# QCopterRC_KEY_Sch.net
KiCad netlist of a schematic drawn in Altium Designer
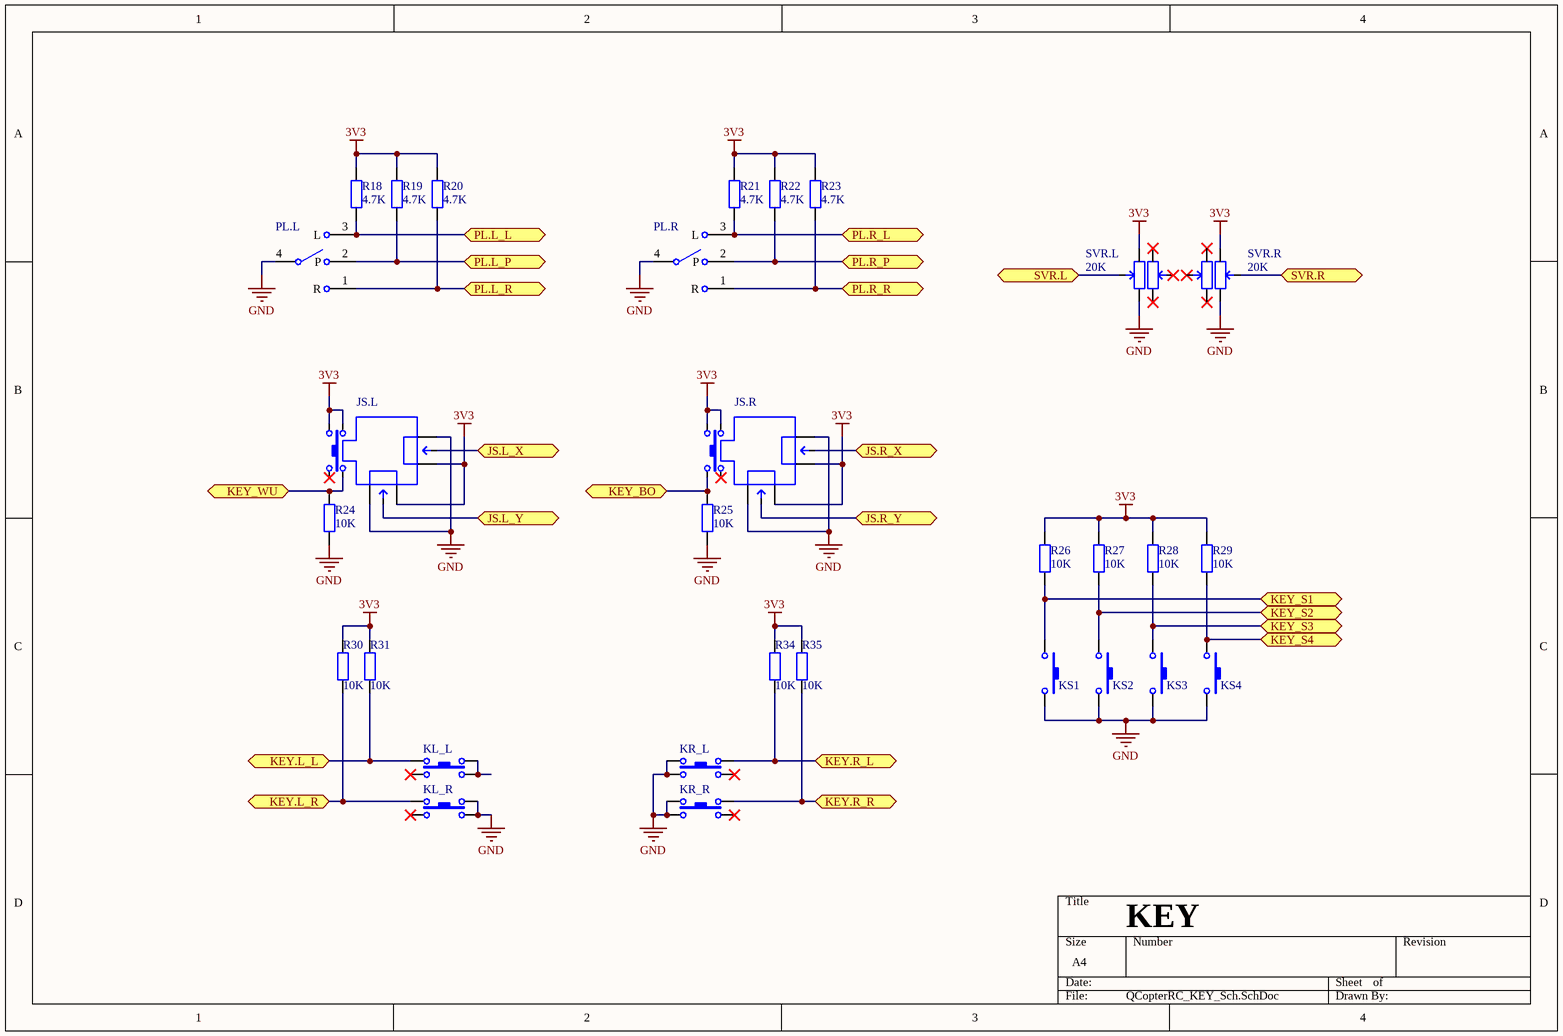
[diagram p0: QCopterRC_KEY_Sch.SchDoc]

(export (version "E")
  (design (tool "Eeschema 10.0.6"))
  (components
    (comp (ref "JS.L")
      (value "JoyStick")
      (footprint "PCB_Switch:JoyStick")
      (libsource (lib "SCH_Switch") (part "JoyStick"))
    )
    (comp (ref "JS.R")
      (value "JoyStick")
      (footprint "PCB_Switch:JoyStick")
      (libsource (lib "SCH_Switch") (part "JoyStick"))
    )
    (comp (ref "KL_L")
      (value "BT_TACT_12X12_D180")
      (footprint "PCB_Switch:BT_TACT_12X12_D180")
      (description "Switch")
      (libsource (lib "SCH_Switch") (part "BT_TACT_12X12_D180"))
    )
    (comp (ref "KL_R")
      (value "BT_TACT_12X12_D180")
      (footprint "PCB_Switch:BT_TACT_12X12_D180")
      (description "Switch")
      (libsource (lib "SCH_Switch") (part "BT_TACT_12X12_D180"))
    )
    (comp (ref "KR_L")
      (value "BT_TACT_12X12_D180")
      (footprint "PCB_Switch:BT_TACT_12X12_D180")
      (description "Switch")
      (libsource (lib "SCH_Switch") (part "BT_TACT_12X12_D180"))
    )
    (comp (ref "KR_R")
      (value "BT_TACT_12X12_D180")
      (footprint "PCB_Switch:BT_TACT_12X12_D180")
      (description "Switch")
      (libsource (lib "SCH_Switch") (part "BT_TACT_12X12_D180"))
    )
    (comp (ref "KS1")
      (value "BT_TACT_3x6_180")
      (footprint "PCB_Switch:BT_TACT_3x6_180")
      (description "Switch")
      (libsource (lib "SCH_Switch") (part "BT_TACT_3x6_180"))
    )
    (comp (ref "KS2")
      (value "BT_TACT_3x6_180")
      (footprint "PCB_Switch:BT_TACT_3x6_180")
      (description "Switch")
      (libsource (lib "SCH_Switch") (part "BT_TACT_3x6_180"))
    )
    (comp (ref "KS3")
      (value "BT_TACT_3x6_180")
      (footprint "PCB_Switch:BT_TACT_3x6_180")
      (description "Switch")
      (libsource (lib "SCH_Switch") (part "BT_TACT_3x6_180"))
    )
    (comp (ref "KS4")
      (value "BT_TACT_3x6_180")
      (footprint "PCB_Switch:BT_TACT_3x6_180")
      (description "Switch")
      (libsource (lib "SCH_Switch") (part "BT_TACT_3x6_180"))
    )
    (comp (ref "PL.L")
      (value "BT_PushLever_11*12_90")
      (footprint "PCB_Switch:BT_PushLever_11*12_90")
      (description "Switch")
      (libsource (lib "SCH_Switch") (part "BT_PushLever_11*12_90"))
    )
    (comp (ref "PL.R")
      (value "BT_PushLever_11*12_90")
      (footprint "PCB_Switch:BT_PushLever_11*12_90")
      (description "Switch")
      (libsource (lib "SCH_Switch") (part "BT_PushLever_11*12_90"))
    )
    (comp (ref "R18")
      (value "4.7K")
      (footprint "PCB_Passive:RES_0603")
      (description "Resistor")
      (fields (field (name "Comment") "Res_0603"))
      (libsource (lib "SCH_Passive") (part "Res_0603"))
    )
    (comp (ref "R19")
      (value "4.7K")
      (footprint "PCB_Passive:RES_0603")
      (description "Resistor")
      (fields (field (name "Comment") "Res_0603"))
      (libsource (lib "SCH_Passive") (part "Res_0603"))
    )
    (comp (ref "R20")
      (value "4.7K")
      (footprint "PCB_Passive:RES_0603")
      (description "Resistor")
      (fields (field (name "Comment") "Res_0603"))
      (libsource (lib "SCH_Passive") (part "Res_0603"))
    )
    (comp (ref "R21")
      (value "4.7K")
      (footprint "PCB_Passive:RES_0603")
      (description "Resistor")
      (fields (field (name "Comment") "Res_0603"))
      (libsource (lib "SCH_Passive") (part "Res_0603"))
    )
    (comp (ref "R22")
      (value "4.7K")
      (footprint "PCB_Passive:RES_0603")
      (description "Resistor")
      (fields (field (name "Comment") "Res_0603"))
      (libsource (lib "SCH_Passive") (part "Res_0603"))
    )
    (comp (ref "R23")
      (value "4.7K")
      (footprint "PCB_Passive:RES_0603")
      (description "Resistor")
      (fields (field (name "Comment") "Res_0603"))
      (libsource (lib "SCH_Passive") (part "Res_0603"))
    )
    (comp (ref "R24")
      (value "10K")
      (footprint "PCB_Passive:RES_0603")
      (description "Resistor")
      (fields (field (name "Comment") "Res_0603"))
      (libsource (lib "SCH_Passive") (part "Res_0603"))
    )
    (comp (ref "R25")
      (value "10K")
      (footprint "PCB_Passive:RES_0603")
      (description "Resistor")
      (fields (field (name "Comment") "Res_0603"))
      (libsource (lib "SCH_Passive") (part "Res_0603"))
    )
    (comp (ref "R26")
      (value "10K")
      (footprint "PCB_Passive:RES_0603")
      (description "Resistor")
      (fields (field (name "Comment") "Res_0603"))
      (libsource (lib "SCH_Passive") (part "Res_0603"))
    )
    (comp (ref "R27")
      (value "10K")
      (footprint "PCB_Passive:RES_0603")
      (description "Resistor")
      (fields (field (name "Comment") "Res_0603"))
      (libsource (lib "SCH_Passive") (part "Res_0603"))
    )
    (comp (ref "R28")
      (value "10K")
      (footprint "PCB_Passive:RES_0603")
      (description "Resistor")
      (fields (field (name "Comment") "Res_0603"))
      (libsource (lib "SCH_Passive") (part "Res_0603"))
    )
    (comp (ref "R29")
      (value "10K")
      (footprint "PCB_Passive:RES_0603")
      (description "Resistor")
      (fields (field (name "Comment") "Res_0603"))
      (libsource (lib "SCH_Passive") (part "Res_0603"))
    )
    (comp (ref "R30")
      (value "10K")
      (footprint "PCB_Passive:RES_0603")
      (description "Resistor")
      (fields (field (name "Comment") "Res_0603"))
      (libsource (lib "SCH_Passive") (part "Res_0603"))
    )
    (comp (ref "R31")
      (value "10K")
      (footprint "PCB_Passive:RES_0603")
      (description "Resistor")
      (fields (field (name "Comment") "Res_0603"))
      (libsource (lib "SCH_Passive") (part "Res_0603"))
    )
    (comp (ref "R34")
      (value "10K")
      (footprint "PCB_Passive:RES_0603")
      (description "Resistor")
      (fields (field (name "Comment") "Res_0603"))
      (libsource (lib "SCH_Passive") (part "Res_0603"))
    )
    (comp (ref "R35")
      (value "10K")
      (footprint "PCB_Passive:RES_0603")
      (description "Resistor")
      (fields (field (name "Comment") "Res_0603"))
      (libsource (lib "SCH_Passive") (part "Res_0603"))
    )
    (comp (ref "SVR.L")
      (value "20K")
      (footprint "PCB_Passive:RES_45MM_DIP")
      (description "Resistor")
      (fields (field (name "Comment") "RES_45MM_DIP"))
      (libsource (lib "SCH_Passive") (part "RES_45MM_DIP"))
    )
    (comp (ref "SVR.R")
      (value "20K")
      (footprint "PCB_Passive:RES_45MM_DIP")
      (description "Resistor")
      (fields (field (name "Comment") "RES_45MM_DIP"))
      (libsource (lib "SCH_Passive") (part "RES_45MM_DIP"))
    )
  )
  (nets
    (net (code "1") (name "/JS.L_X") (class "Default")
      (node (ref "JS.L") (pin "5") (pinfunction "5_5") (pintype "passive"))
    )
    (net (code "2") (name "/JS.L_Y") (class "Default")
      (node (ref "JS.L") (pin "2") (pinfunction "2_2") (pintype "passive"))
    )
    (net (code "3") (name "/JS.R_X") (class "Default")
      (node (ref "JS.R") (pin "5") (pinfunction "5_5") (pintype "passive"))
    )
    (net (code "4") (name "/JS.R_Y") (class "Default")
      (node (ref "JS.R") (pin "2") (pinfunction "2_2") (pintype "passive"))
    )
    (net (code "5") (name "/KEY.L_L") (class "Default")
      (node (ref "KL_L") (pin "1") (pinfunction "1_1") (pintype "passive"))
      (node (ref "R31") (pin "2") (pinfunction "2_2") (pintype "passive"))
    )
    (net (code "6") (name "/KEY.L_R") (class "Default")
      (node (ref "KL_R") (pin "1") (pinfunction "1_1") (pintype "passive"))
      (node (ref "R30") (pin "2") (pinfunction "2_2") (pintype "passive"))
    )
    (net (code "7") (name "/KEY.R_L") (class "Default")
      (node (ref "KR_L") (pin "2") (pinfunction "2_2") (pintype "passive"))
      (node (ref "R34") (pin "2") (pinfunction "2_2") (pintype "passive"))
    )
    (net (code "8") (name "/KEY.R_R") (class "Default")
      (node (ref "KR_R") (pin "2") (pinfunction "2_2") (pintype "passive"))
      (node (ref "R35") (pin "2") (pinfunction "2_2") (pintype "passive"))
    )
    (net (code "9") (name "/KEY_BO") (class "Default")
      (node (ref "JS.R") (pin "8") (pinfunction "8_8") (pintype "passive"))
      (node (ref "R25") (pin "1") (pinfunction "1_1") (pintype "passive"))
    )
    (net (code "10") (name "/KEY_S1") (class "Default")
      (node (ref "KS1") (pin "1") (pinfunction "1_1") (pintype "passive"))
      (node (ref "R26") (pin "2") (pinfunction "2_2") (pintype "passive"))
    )
    (net (code "11") (name "/KEY_S2") (class "Default")
      (node (ref "KS2") (pin "1") (pinfunction "1_1") (pintype "passive"))
      (node (ref "R27") (pin "2") (pinfunction "2_2") (pintype "passive"))
    )
    (net (code "12") (name "/KEY_S3") (class "Default")
      (node (ref "KS3") (pin "1") (pinfunction "1_1") (pintype "passive"))
      (node (ref "R28") (pin "2") (pinfunction "2_2") (pintype "passive"))
    )
    (net (code "13") (name "/KEY_S4") (class "Default")
      (node (ref "KS4") (pin "1") (pinfunction "1_1") (pintype "passive"))
      (node (ref "R29") (pin "2") (pinfunction "2_2") (pintype "passive"))
    )
    (net (code "14") (name "/KEY_WU") (class "Default")
      (node (ref "JS.L") (pin "10") (pinfunction "10_10") (pintype "passive"))
      (node (ref "R24") (pin "1") (pinfunction "1_1") (pintype "passive"))
    )
    (net (code "15") (name "/PL.L_L") (class "Default")
      (node (ref "PL.L") (pin "3") (pinfunction "L_3") (pintype "passive"))
      (node (ref "R18") (pin "2") (pinfunction "2_2") (pintype "passive"))
    )
    (net (code "16") (name "/PL.L_P") (class "Default")
      (node (ref "PL.L") (pin "2") (pinfunction "P_2") (pintype "passive"))
      (node (ref "R19") (pin "2") (pinfunction "2_2") (pintype "passive"))
    )
    (net (code "17") (name "/PL.L_R") (class "Default")
      (node (ref "PL.L") (pin "1") (pinfunction "R_1") (pintype "passive"))
      (node (ref "R20") (pin "2") (pinfunction "2_2") (pintype "passive"))
    )
    (net (code "18") (name "/PL.R_L") (class "Default")
      (node (ref "PL.R") (pin "3") (pinfunction "L_3") (pintype "passive"))
      (node (ref "R21") (pin "2") (pinfunction "2_2") (pintype "passive"))
    )
    (net (code "19") (name "/PL.R_P") (class "Default")
      (node (ref "PL.R") (pin "2") (pinfunction "P_2") (pintype "passive"))
      (node (ref "R22") (pin "2") (pinfunction "2_2") (pintype "passive"))
    )
    (net (code "20") (name "/PL.R_R") (class "Default")
      (node (ref "PL.R") (pin "1") (pinfunction "R_1") (pintype "passive"))
      (node (ref "R23") (pin "2") (pinfunction "2_2") (pintype "passive"))
    )
    (net (code "21") (name "/SVR.L") (class "Default")
      (node (ref "SVR.L") (pin "2") (pinfunction "W_2") (pintype "passive"))
    )
    (net (code "22") (name "/SVR.R") (class "Default")
      (node (ref "SVR.R") (pin "4") (pinfunction "W_4") (pintype "passive"))
    )
    (net (code "23") (name "3V3") (class "Default")
      (node (ref "JS.L") (pin "3") (pinfunction "3_3") (pintype "passive"))
      (node (ref "JS.L") (pin "4") (pinfunction "4_4") (pintype "passive"))
      (node (ref "JS.L") (pin "7") (pinfunction "7_7") (pintype "passive"))
      (node (ref "JS.L") (pin "9") (pinfunction "9_9") (pintype "passive"))
      (node (ref "JS.R") (pin "3") (pinfunction "3_3") (pintype "passive"))
      (node (ref "JS.R") (pin "4") (pinfunction "4_4") (pintype "passive"))
      (node (ref "JS.R") (pin "7") (pinfunction "7_7") (pintype "passive"))
      (node (ref "JS.R") (pin "9") (pinfunction "9_9") (pintype "passive"))
      (node (ref "R18") (pin "1") (pinfunction "1_1") (pintype "passive"))
      (node (ref "R19") (pin "1") (pinfunction "1_1") (pintype "passive"))
      (node (ref "R20") (pin "1") (pinfunction "1_1") (pintype "passive"))
      (node (ref "R21") (pin "1") (pinfunction "1_1") (pintype "passive"))
      (node (ref "R22") (pin "1") (pinfunction "1_1") (pintype "passive"))
      (node (ref "R23") (pin "1") (pinfunction "1_1") (pintype "passive"))
      (node (ref "R26") (pin "1") (pinfunction "1_1") (pintype "passive"))
      (node (ref "R27") (pin "1") (pinfunction "1_1") (pintype "passive"))
      (node (ref "R28") (pin "1") (pinfunction "1_1") (pintype "passive"))
      (node (ref "R29") (pin "1") (pinfunction "1_1") (pintype "passive"))
      (node (ref "R30") (pin "1") (pinfunction "1_1") (pintype "passive"))
      (node (ref "R31") (pin "1") (pinfunction "1_1") (pintype "passive"))
      (node (ref "R34") (pin "1") (pinfunction "1_1") (pintype "passive"))
      (node (ref "R35") (pin "1") (pinfunction "1_1") (pintype "passive"))
      (node (ref "SVR.L") (pin "1") (pinfunction "U_1") (pintype "passive"))
      (node (ref "SVR.R") (pin "3") (pinfunction "U_3") (pintype "passive"))
    )
    (net (code "24") (name "GND") (class "Default")
      (node (ref "JS.L") (pin "1") (pinfunction "1_1") (pintype "passive"))
      (node (ref "JS.L") (pin "6") (pinfunction "6_6") (pintype "passive"))
      (node (ref "JS.R") (pin "1") (pinfunction "1_1") (pintype "passive"))
      (node (ref "JS.R") (pin "6") (pinfunction "6_6") (pintype "passive"))
      (node (ref "KL_R") (pin "2") (pinfunction "2_2") (pintype "passive"))
      (node (ref "KL_R") (pin "4") (pinfunction "4_4") (pintype "passive"))
      (node (ref "KR_L") (pin "1") (pinfunction "1_1") (pintype "passive"))
      (node (ref "KR_L") (pin "3") (pinfunction "3_3") (pintype "passive"))
      (node (ref "KR_R") (pin "1") (pinfunction "1_1") (pintype "passive"))
      (node (ref "KR_R") (pin "3") (pinfunction "3_3") (pintype "passive"))
      (node (ref "KS1") (pin "2") (pinfunction "2_2") (pintype "passive"))
      (node (ref "KS2") (pin "2") (pinfunction "2_2") (pintype "passive"))
      (node (ref "KS3") (pin "2") (pinfunction "2_2") (pintype "passive"))
      (node (ref "KS4") (pin "2") (pinfunction "2_2") (pintype "passive"))
      (node (ref "PL.L") (pin "4") (pinfunction "4_4") (pintype "passive"))
      (node (ref "PL.R") (pin "4") (pinfunction "4_4") (pintype "passive"))
      (node (ref "R24") (pin "2") (pinfunction "2_2") (pintype "passive"))
      (node (ref "R25") (pin "2") (pinfunction "2_2") (pintype "passive"))
      (node (ref "SVR.L") (pin "5") (pinfunction "D_5") (pintype "passive"))
      (node (ref "SVR.R") (pin "6") (pinfunction "D_6") (pintype "passive"))
    )
    (net (code "25") (name "Net-(KL_L-Pad2)") (class "Default")
      (node (ref "KL_L") (pin "2") (pinfunction "2_2") (pintype "passive"))
      (node (ref "KL_L") (pin "4") (pinfunction "4_4") (pintype "passive"))
    )
    (net (code "26") (name "unconnected-(JS.L-Pad8)") (class "Default")
      (node (ref "JS.L") (pin "8") (pinfunction "8_8") (pintype "passive+no_connect"))
    )
    (net (code "27") (name "unconnected-(JS.R-Pad10)") (class "Default")
      (node (ref "JS.R") (pin "10") (pinfunction "10_10") (pintype "passive+no_connect"))
    )
    (net (code "28") (name "unconnected-(KL_L-Pad3)") (class "Default")
      (node (ref "KL_L") (pin "3") (pinfunction "3_3") (pintype "passive+no_connect"))
    )
    (net (code "29") (name "unconnected-(KL_R-Pad3)") (class "Default")
      (node (ref "KL_R") (pin "3") (pinfunction "3_3") (pintype "passive+no_connect"))
    )
    (net (code "30") (name "unconnected-(KR_L-Pad4)") (class "Default")
      (node (ref "KR_L") (pin "4") (pinfunction "4_4") (pintype "passive+no_connect"))
    )
    (net (code "31") (name "unconnected-(KR_R-Pad4)") (class "Default")
      (node (ref "KR_R") (pin "4") (pinfunction "4_4") (pintype "passive+no_connect"))
    )
    (net (code "32") (name "unconnected-(SVR.L-D-Pad6)") (class "Default")
      (node (ref "SVR.L") (pin "6") (pinfunction "D_6") (pintype "passive+no_connect"))
    )
    (net (code "33") (name "unconnected-(SVR.L-U-Pad3)") (class "Default")
      (node (ref "SVR.L") (pin "3") (pinfunction "U_3") (pintype "passive+no_connect"))
    )
    (net (code "34") (name "unconnected-(SVR.L-W-Pad4)") (class "Default")
      (node (ref "SVR.L") (pin "4") (pinfunction "W_4") (pintype "passive+no_connect"))
    )
    (net (code "35") (name "unconnected-(SVR.R-D-Pad5)") (class "Default")
      (node (ref "SVR.R") (pin "5") (pinfunction "D_5") (pintype "passive+no_connect"))
    )
    (net (code "36") (name "unconnected-(SVR.R-U-Pad1)") (class "Default")
      (node (ref "SVR.R") (pin "1") (pinfunction "U_1") (pintype "passive+no_connect"))
    )
    (net (code "37") (name "unconnected-(SVR.R-W-Pad2)") (class "Default")
      (node (ref "SVR.R") (pin "2") (pinfunction "W_2") (pintype "passive+no_connect"))
    )
  )
)
